# dip_hat_trick.net
KiCad netlist of a schematic drawn in EAGLE
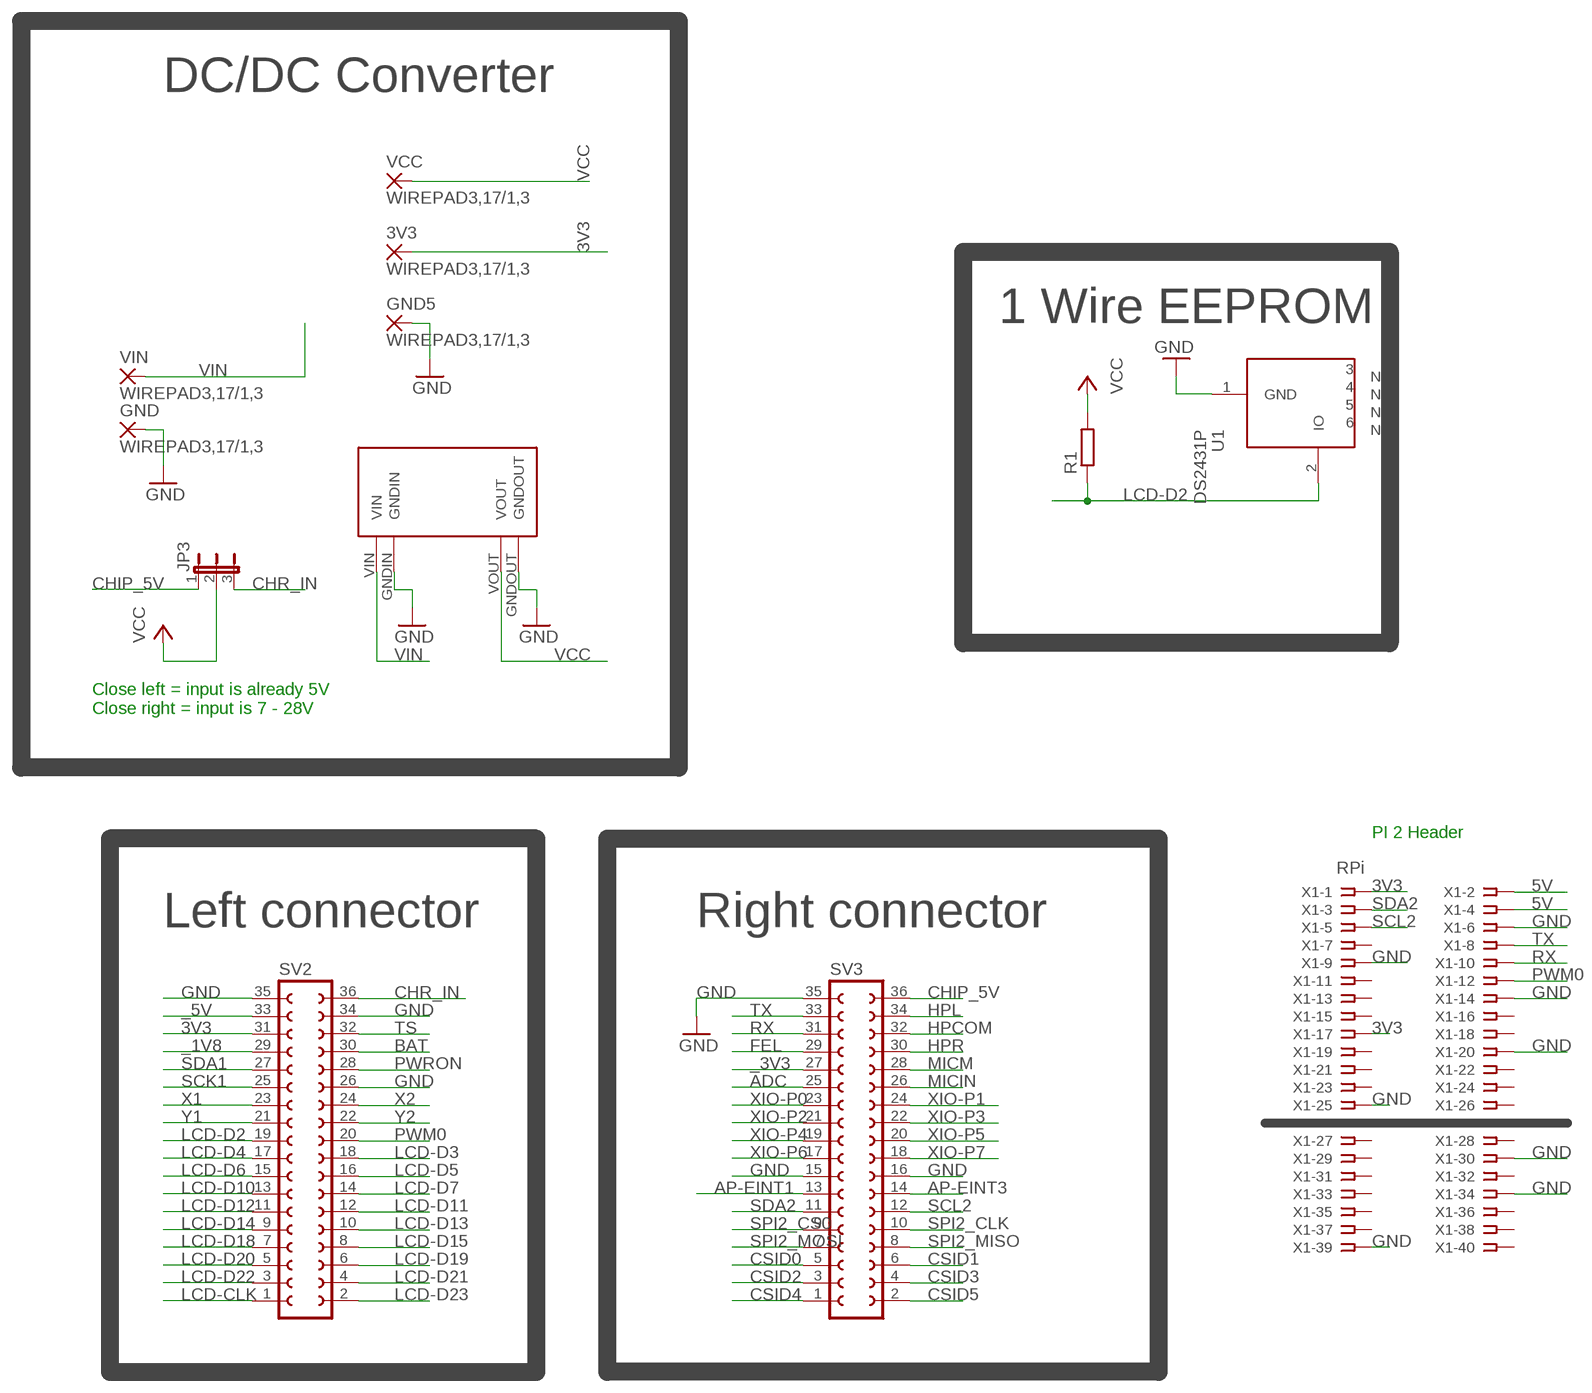
[diagram p0: schematic, sheet 1]

(export (version "E")
  (design (tool "Eeschema 10.0.6"))
  (components
    (comp (ref "3V3")
      (value "WIREPAD3,17/1,3")
      (footprint "eagle-import:3,17_1,3")
      (libsource (lib "eagle-import") (part "WIREPAD3,17/1,3"))
    )
    (comp (ref "GND")
      (value "WIREPAD3,17/1,3")
      (footprint "eagle-import:3,17_1,3")
      (libsource (lib "eagle-import") (part "WIREPAD3,17/1,3"))
    )
    (comp (ref "GND5")
      (value "WIREPAD3,17/1,3")
      (footprint "eagle-import:3,17_1,3")
      (libsource (lib "eagle-import") (part "WIREPAD3,17/1,3"))
    )
    (comp (ref "JP3")
      (value "JP2E")
      (footprint "eagle-import:JP2")
      (libsource (lib "eagle-import") (part "JP2E"))
    )
    (comp (ref "R1")
      (value "R-EU_R0805")
      (footprint "eagle-import:R0805")
      (libsource (lib "eagle-import") (part "R-EU_R0805"))
    )
    (comp (ref "SV2")
      (value "FE18-2")
      (footprint "eagle-import:FE18-2")
      (libsource (lib "eagle-import") (part "FE18-2"))
    )
    (comp (ref "SV3")
      (value "FE18-2")
      (footprint "eagle-import:FE18-2")
      (libsource (lib "eagle-import") (part "FE18-2"))
    )
    (comp (ref "U$9")
      (value "MP1584EN_FRAMELESS")
      (footprint "eagle-import:MP1584EN_FRAMELESS")
      (libsource (lib "eagle-import") (part "MP1584EN_FRAMELESS"))
    )
    (comp (ref "U1")
      (value "DS2431P")
      (footprint "eagle-import:TSOC6")
      (fields (field (name "MFG") "DIGIKEY") (field (name "VENDOR_PART_NUMBER") "DS2431P+T&R"))
      (libsource (lib "eagle-import") (part "DS2431P"))
    )
    (comp (ref "VCC")
      (value "WIREPAD3,17/1,3")
      (footprint "eagle-import:3,17_1,3")
      (libsource (lib "eagle-import") (part "WIREPAD3,17/1,3"))
    )
    (comp (ref "VIN")
      (value "WIREPAD3,17/1,3")
      (footprint "eagle-import:3,17_1,3")
      (libsource (lib "eagle-import") (part "WIREPAD3,17/1,3"))
    )
    (comp (ref "X1")
      (value "RPi")
      (footprint "eagle-import:SSW-120-02-S-D")
      (fields (field (name "MPN") "SSW-120-02-S-D"))
      (libsource (lib "eagle-import") (part "SSW-120-02-S-D"))
    )
  )
  (nets
    (net (code "1") (name "/3V3") (class "Default")
      (node (ref "3V3") (pin "1") (pinfunction "P_1") (pintype "passive"))
      (node (ref "SV2") (pin "31") (pinfunction "31_31") (pintype "passive"))
      (node (ref "X1") (pin "1") (pinfunction "1_1") (pintype "passive"))
      (node (ref "X1") (pin "17") (pinfunction "1_17") (pintype "passive"))
    )
    (net (code "2") (name "/5V") (class "Default")
      (node (ref "X1") (pin "2") (pinfunction "1_2") (pintype "passive"))
      (node (ref "X1") (pin "4") (pinfunction "1_4") (pintype "passive"))
    )
    (net (code "3") (name "/ADC") (class "Default")
      (node (ref "SV3") (pin "25") (pinfunction "25_25") (pintype "passive"))
    )
    (net (code "4") (name "/AP-EINT1") (class "Default")
      (node (ref "SV3") (pin "13") (pinfunction "13_13") (pintype "passive"))
    )
    (net (code "5") (name "/AP-EINT3") (class "Default")
      (node (ref "SV3") (pin "14") (pinfunction "14_14") (pintype "passive"))
    )
    (net (code "6") (name "/BAT") (class "Default")
      (node (ref "SV2") (pin "30") (pinfunction "30_30") (pintype "passive"))
    )
    (net (code "7") (name "/CHIP_5V") (class "Default")
      (node (ref "JP3") (pin "1") (pinfunction "1_1") (pintype "passive"))
      (node (ref "SV3") (pin "36") (pinfunction "36_36") (pintype "passive"))
    )
    (net (code "8") (name "/CHR_IN") (class "Default")
      (node (ref "JP3") (pin "3") (pinfunction "3_3") (pintype "passive"))
      (node (ref "SV2") (pin "36") (pinfunction "36_36") (pintype "passive"))
    )
    (net (code "9") (name "/CSID0") (class "Default")
      (node (ref "SV3") (pin "5") (pinfunction "5_5") (pintype "passive"))
    )
    (net (code "10") (name "/CSID1") (class "Default")
      (node (ref "SV3") (pin "6") (pinfunction "6_6") (pintype "passive"))
    )
    (net (code "11") (name "/CSID2") (class "Default")
      (node (ref "SV3") (pin "3") (pinfunction "3_3") (pintype "passive"))
    )
    (net (code "12") (name "/CSID3") (class "Default")
      (node (ref "SV3") (pin "4") (pinfunction "4_4") (pintype "passive"))
    )
    (net (code "13") (name "/CSID4") (class "Default")
      (node (ref "SV3") (pin "1") (pinfunction "1_1") (pintype "passive"))
    )
    (net (code "14") (name "/CSID5") (class "Default")
      (node (ref "SV3") (pin "2") (pinfunction "2_2") (pintype "passive"))
    )
    (net (code "15") (name "/FEL") (class "Default")
      (node (ref "SV3") (pin "29") (pinfunction "29_29") (pintype "passive"))
    )
    (net (code "16") (name "/HPCOM") (class "Default")
      (node (ref "SV3") (pin "32") (pinfunction "32_32") (pintype "passive"))
    )
    (net (code "17") (name "/HPL") (class "Default")
      (node (ref "SV3") (pin "34") (pinfunction "34_34") (pintype "passive"))
    )
    (net (code "18") (name "/HPR") (class "Default")
      (node (ref "SV3") (pin "30") (pinfunction "30_30") (pintype "passive"))
    )
    (net (code "19") (name "/LCD-CLK") (class "Default")
      (node (ref "SV2") (pin "1") (pinfunction "1_1") (pintype "passive"))
    )
    (net (code "20") (name "/LCD-D2") (class "Default")
      (node (ref "R1") (pin "1") (pinfunction "1_1") (pintype "passive"))
      (node (ref "SV2") (pin "19") (pinfunction "19_19") (pintype "passive"))
      (node (ref "U1") (pin "2") (pinfunction "IO_2") (pintype "bidirectional"))
    )
    (net (code "21") (name "/LCD-D3") (class "Default")
      (node (ref "SV2") (pin "18") (pinfunction "18_18") (pintype "passive"))
    )
    (net (code "22") (name "/LCD-D4") (class "Default")
      (node (ref "SV2") (pin "17") (pinfunction "17_17") (pintype "passive"))
    )
    (net (code "23") (name "/LCD-D5") (class "Default")
      (node (ref "SV2") (pin "16") (pinfunction "16_16") (pintype "passive"))
    )
    (net (code "24") (name "/LCD-D6") (class "Default")
      (node (ref "SV2") (pin "15") (pinfunction "15_15") (pintype "passive"))
    )
    (net (code "25") (name "/LCD-D7") (class "Default")
      (node (ref "SV2") (pin "14") (pinfunction "14_14") (pintype "passive"))
    )
    (net (code "26") (name "/LCD-D10") (class "Default")
      (node (ref "SV2") (pin "13") (pinfunction "13_13") (pintype "passive"))
    )
    (net (code "27") (name "/LCD-D11") (class "Default")
      (node (ref "SV2") (pin "12") (pinfunction "12_12") (pintype "passive"))
    )
    (net (code "28") (name "/LCD-D12") (class "Default")
      (node (ref "SV2") (pin "11") (pinfunction "11_11") (pintype "passive"))
    )
    (net (code "29") (name "/LCD-D13") (class "Default")
      (node (ref "SV2") (pin "10") (pinfunction "10_10") (pintype "passive"))
    )
    (net (code "30") (name "/LCD-D14") (class "Default")
      (node (ref "SV2") (pin "9") (pinfunction "9_9") (pintype "passive"))
    )
    (net (code "31") (name "/LCD-D15") (class "Default")
      (node (ref "SV2") (pin "8") (pinfunction "8_8") (pintype "passive"))
    )
    (net (code "32") (name "/LCD-D18") (class "Default")
      (node (ref "SV2") (pin "7") (pinfunction "7_7") (pintype "passive"))
    )
    (net (code "33") (name "/LCD-D19") (class "Default")
      (node (ref "SV2") (pin "6") (pinfunction "6_6") (pintype "passive"))
    )
    (net (code "34") (name "/LCD-D20") (class "Default")
      (node (ref "SV2") (pin "5") (pinfunction "5_5") (pintype "passive"))
    )
    (net (code "35") (name "/LCD-D21") (class "Default")
      (node (ref "SV2") (pin "4") (pinfunction "4_4") (pintype "passive"))
    )
    (net (code "36") (name "/LCD-D22") (class "Default")
      (node (ref "SV2") (pin "3") (pinfunction "3_3") (pintype "passive"))
    )
    (net (code "37") (name "/LCD-D23") (class "Default")
      (node (ref "SV2") (pin "2") (pinfunction "2_2") (pintype "passive"))
    )
    (net (code "38") (name "/MICIN") (class "Default")
      (node (ref "SV3") (pin "26") (pinfunction "26_26") (pintype "passive"))
    )
    (net (code "39") (name "/MICM") (class "Default")
      (node (ref "SV3") (pin "28") (pinfunction "28_28") (pintype "passive"))
    )
    (net (code "40") (name "/PWM0") (class "Default")
      (node (ref "SV2") (pin "20") (pinfunction "20_20") (pintype "passive"))
      (node (ref "X1") (pin "12") (pinfunction "1_12") (pintype "passive"))
    )
    (net (code "41") (name "/PWRON") (class "Default")
      (node (ref "SV2") (pin "28") (pinfunction "28_28") (pintype "passive"))
    )
    (net (code "42") (name "/RX") (class "Default")
      (node (ref "SV3") (pin "31") (pinfunction "31_31") (pintype "passive"))
      (node (ref "X1") (pin "10") (pinfunction "1_10") (pintype "passive"))
    )
    (net (code "43") (name "/SCK1") (class "Default")
      (node (ref "SV2") (pin "25") (pinfunction "25_25") (pintype "passive"))
    )
    (net (code "44") (name "/SCL2") (class "Default")
      (node (ref "SV3") (pin "12") (pinfunction "12_12") (pintype "passive"))
      (node (ref "X1") (pin "5") (pinfunction "1_5") (pintype "passive"))
    )
    (net (code "45") (name "/SDA1") (class "Default")
      (node (ref "SV2") (pin "27") (pinfunction "27_27") (pintype "passive"))
    )
    (net (code "46") (name "/SDA2") (class "Default")
      (node (ref "SV3") (pin "11") (pinfunction "11_11") (pintype "passive"))
      (node (ref "X1") (pin "3") (pinfunction "1_3") (pintype "passive"))
    )
    (net (code "47") (name "/SPI2_CLK") (class "Default")
      (node (ref "SV3") (pin "10") (pinfunction "10_10") (pintype "passive"))
    )
    (net (code "48") (name "/SPI2_CS0") (class "Default")
      (node (ref "SV3") (pin "9") (pinfunction "9_9") (pintype "passive"))
    )
    (net (code "49") (name "/SPI2_MISO") (class "Default")
      (node (ref "SV3") (pin "8") (pinfunction "8_8") (pintype "passive"))
    )
    (net (code "50") (name "/SPI2_MOSI") (class "Default")
      (node (ref "SV3") (pin "7") (pinfunction "7_7") (pintype "passive"))
    )
    (net (code "51") (name "/TS") (class "Default")
      (node (ref "SV2") (pin "32") (pinfunction "32_32") (pintype "passive"))
    )
    (net (code "52") (name "/TX") (class "Default")
      (node (ref "SV3") (pin "33") (pinfunction "33_33") (pintype "passive"))
      (node (ref "X1") (pin "8") (pinfunction "1_8") (pintype "passive"))
    )
    (net (code "53") (name "/VIN") (class "Default")
      (node (ref "U$9") (pin "VIN") (pinfunction "VIN_VIN") (pintype "power_in"))
      (node (ref "VIN") (pin "1") (pinfunction "P_1") (pintype "passive"))
    )
    (net (code "54") (name "/X1") (class "Default")
      (node (ref "SV2") (pin "23") (pinfunction "23_23") (pintype "passive"))
    )
    (net (code "55") (name "/X2") (class "Default")
      (node (ref "SV2") (pin "24") (pinfunction "24_24") (pintype "passive"))
    )
    (net (code "56") (name "/XIO-P0") (class "Default")
      (node (ref "SV3") (pin "23") (pinfunction "23_23") (pintype "passive"))
    )
    (net (code "57") (name "/XIO-P1") (class "Default")
      (node (ref "SV3") (pin "24") (pinfunction "24_24") (pintype "passive"))
    )
    (net (code "58") (name "/XIO-P2") (class "Default")
      (node (ref "SV3") (pin "21") (pinfunction "21_21") (pintype "passive"))
    )
    (net (code "59") (name "/XIO-P3") (class "Default")
      (node (ref "SV3") (pin "22") (pinfunction "22_22") (pintype "passive"))
    )
    (net (code "60") (name "/XIO-P4") (class "Default")
      (node (ref "SV3") (pin "19") (pinfunction "19_19") (pintype "passive"))
    )
    (net (code "61") (name "/XIO-P5") (class "Default")
      (node (ref "SV3") (pin "20") (pinfunction "20_20") (pintype "passive"))
    )
    (net (code "62") (name "/XIO-P6") (class "Default")
      (node (ref "SV3") (pin "17") (pinfunction "17_17") (pintype "passive"))
    )
    (net (code "63") (name "/XIO-P7") (class "Default")
      (node (ref "SV3") (pin "18") (pinfunction "18_18") (pintype "passive"))
    )
    (net (code "64") (name "/Y1") (class "Default")
      (node (ref "SV2") (pin "21") (pinfunction "21_21") (pintype "passive"))
    )
    (net (code "65") (name "/Y2") (class "Default")
      (node (ref "SV2") (pin "22") (pinfunction "22_22") (pintype "passive"))
    )
    (net (code "66") (name "/_1V8") (class "Default")
      (node (ref "SV2") (pin "29") (pinfunction "29_29") (pintype "passive"))
    )
    (net (code "67") (name "/_3V3") (class "Default")
      (node (ref "SV3") (pin "27") (pinfunction "27_27") (pintype "passive"))
    )
    (net (code "68") (name "/_5V") (class "Default")
      (node (ref "SV2") (pin "33") (pinfunction "33_33") (pintype "passive"))
    )
    (net (code "69") (name "GND") (class "Default")
      (node (ref "GND") (pin "1") (pinfunction "P_1") (pintype "passive"))
      (node (ref "GND5") (pin "1") (pinfunction "P_1") (pintype "passive"))
      (node (ref "SV2") (pin "26") (pinfunction "26_26") (pintype "passive"))
      (node (ref "SV2") (pin "34") (pinfunction "34_34") (pintype "passive"))
      (node (ref "SV2") (pin "35") (pinfunction "35_35") (pintype "passive"))
      (node (ref "SV3") (pin "15") (pinfunction "15_15") (pintype "passive"))
      (node (ref "SV3") (pin "16") (pinfunction "16_16") (pintype "passive"))
      (node (ref "SV3") (pin "35") (pinfunction "35_35") (pintype "passive"))
      (node (ref "U$9") (pin "GNDIN") (pinfunction "GNDIN_GNDIN") (pintype "power_in"))
      (node (ref "U$9") (pin "GNDOUT") (pinfunction "GNDOUT_GNDOUT") (pintype "power_in"))
      (node (ref "U1") (pin "1") (pinfunction "GND_1") (pintype "bidirectional"))
      (node (ref "X1") (pin "14") (pinfunction "1_14") (pintype "passive"))
      (node (ref "X1") (pin "20") (pinfunction "1_20") (pintype "passive"))
      (node (ref "X1") (pin "25") (pinfunction "1_25") (pintype "passive"))
      (node (ref "X1") (pin "30") (pinfunction "1_30") (pintype "passive"))
      (node (ref "X1") (pin "34") (pinfunction "1_34") (pintype "passive"))
      (node (ref "X1") (pin "39") (pinfunction "1_39") (pintype "passive"))
      (node (ref "X1") (pin "6") (pinfunction "1_6") (pintype "passive"))
      (node (ref "X1") (pin "9") (pinfunction "1_9") (pintype "passive"))
    )
    (net (code "70") (name "VCC") (class "Default")
      (node (ref "JP3") (pin "2") (pinfunction "2_2") (pintype "passive"))
      (node (ref "R1") (pin "2") (pinfunction "2_2") (pintype "passive"))
      (node (ref "U$9") (pin "VOUT") (pinfunction "VOUT_VOUT") (pintype "power_in"))
      (node (ref "VCC") (pin "1") (pinfunction "P_1") (pintype "passive"))
    )
    (net (code "71") (name "unconnected-(U1-NC-Pad3)") (class "Default")
      (node (ref "U1") (pin "3") (pinfunction "NC_3") (pintype "bidirectional"))
    )
    (net (code "72") (name "unconnected-(U1-NC-Pad4)") (class "Default")
      (node (ref "U1") (pin "4") (pinfunction "NC_4") (pintype "bidirectional"))
    )
    (net (code "73") (name "unconnected-(U1-NC-Pad5)") (class "Default")
      (node (ref "U1") (pin "5") (pinfunction "NC_5") (pintype "bidirectional"))
    )
    (net (code "74") (name "unconnected-(U1-NC-Pad6)") (class "Default")
      (node (ref "U1") (pin "6") (pinfunction "NC_6") (pintype "bidirectional"))
    )
    (net (code "75") (name "unconnected-(X1AA-1-Pad33)") (class "Default")
      (node (ref "X1") (pin "33") (pinfunction "1_33") (pintype "passive"))
    )
    (net (code "76") (name "unconnected-(X1AC-1-Pad35)") (class "Default")
      (node (ref "X1") (pin "35") (pinfunction "1_35") (pintype "passive"))
    )
    (net (code "77") (name "unconnected-(X1AD-1-Pad36)") (class "Default")
      (node (ref "X1") (pin "36") (pinfunction "1_36") (pintype "passive"))
    )
    (net (code "78") (name "unconnected-(X1AE-1-Pad37)") (class "Default")
      (node (ref "X1") (pin "37") (pinfunction "1_37") (pintype "passive"))
    )
    (net (code "79") (name "unconnected-(X1AF-1-Pad38)") (class "Default")
      (node (ref "X1") (pin "38") (pinfunction "1_38") (pintype "passive"))
    )
    (net (code "80") (name "unconnected-(X1AI-1-Pad40)") (class "Default")
      (node (ref "X1") (pin "40") (pinfunction "1_40") (pintype "passive"))
    )
    (net (code "81") (name "unconnected-(X1AL-1-Pad7)") (class "Default")
      (node (ref "X1") (pin "7") (pinfunction "1_7") (pintype "passive"))
    )
    (net (code "82") (name "unconnected-(X1C-1-Pad11)") (class "Default")
      (node (ref "X1") (pin "11") (pinfunction "1_11") (pintype "passive"))
    )
    (net (code "83") (name "unconnected-(X1E-1-Pad13)") (class "Default")
      (node (ref "X1") (pin "13") (pinfunction "1_13") (pintype "passive"))
    )
    (net (code "84") (name "unconnected-(X1G-1-Pad15)") (class "Default")
      (node (ref "X1") (pin "15") (pinfunction "1_15") (pintype "passive"))
    )
    (net (code "85") (name "unconnected-(X1H-1-Pad16)") (class "Default")
      (node (ref "X1") (pin "16") (pinfunction "1_16") (pintype "passive"))
    )
    (net (code "86") (name "unconnected-(X1J-1-Pad18)") (class "Default")
      (node (ref "X1") (pin "18") (pinfunction "1_18") (pintype "passive"))
    )
    (net (code "87") (name "unconnected-(X1K-1-Pad19)") (class "Default")
      (node (ref "X1") (pin "19") (pinfunction "1_19") (pintype "passive"))
    )
    (net (code "88") (name "unconnected-(X1N-1-Pad21)") (class "Default")
      (node (ref "X1") (pin "21") (pinfunction "1_21") (pintype "passive"))
    )
    (net (code "89") (name "unconnected-(X1O-1-Pad22)") (class "Default")
      (node (ref "X1") (pin "22") (pinfunction "1_22") (pintype "passive"))
    )
    (net (code "90") (name "unconnected-(X1P-1-Pad23)") (class "Default")
      (node (ref "X1") (pin "23") (pinfunction "1_23") (pintype "passive"))
    )
    (net (code "91") (name "unconnected-(X1Q-1-Pad24)") (class "Default")
      (node (ref "X1") (pin "24") (pinfunction "1_24") (pintype "passive"))
    )
    (net (code "92") (name "unconnected-(X1S-1-Pad26)") (class "Default")
      (node (ref "X1") (pin "26") (pinfunction "1_26") (pintype "passive"))
    )
    (net (code "93") (name "unconnected-(X1T-1-Pad27)") (class "Default")
      (node (ref "X1") (pin "27") (pinfunction "1_27") (pintype "passive"))
    )
    (net (code "94") (name "unconnected-(X1U-1-Pad28)") (class "Default")
      (node (ref "X1") (pin "28") (pinfunction "1_28") (pintype "passive"))
    )
    (net (code "95") (name "unconnected-(X1V-1-Pad29)") (class "Default")
      (node (ref "X1") (pin "29") (pinfunction "1_29") (pintype "passive"))
    )
    (net (code "96") (name "unconnected-(X1Y-1-Pad31)") (class "Default")
      (node (ref "X1") (pin "31") (pinfunction "1_31") (pintype "passive"))
    )
    (net (code "97") (name "unconnected-(X1Z-1-Pad32)") (class "Default")
      (node (ref "X1") (pin "32") (pinfunction "1_32") (pintype "passive"))
    )
  )
)
